# SensorNodeUsb.net
KiCad netlist of a schematic drawn in EAGLE
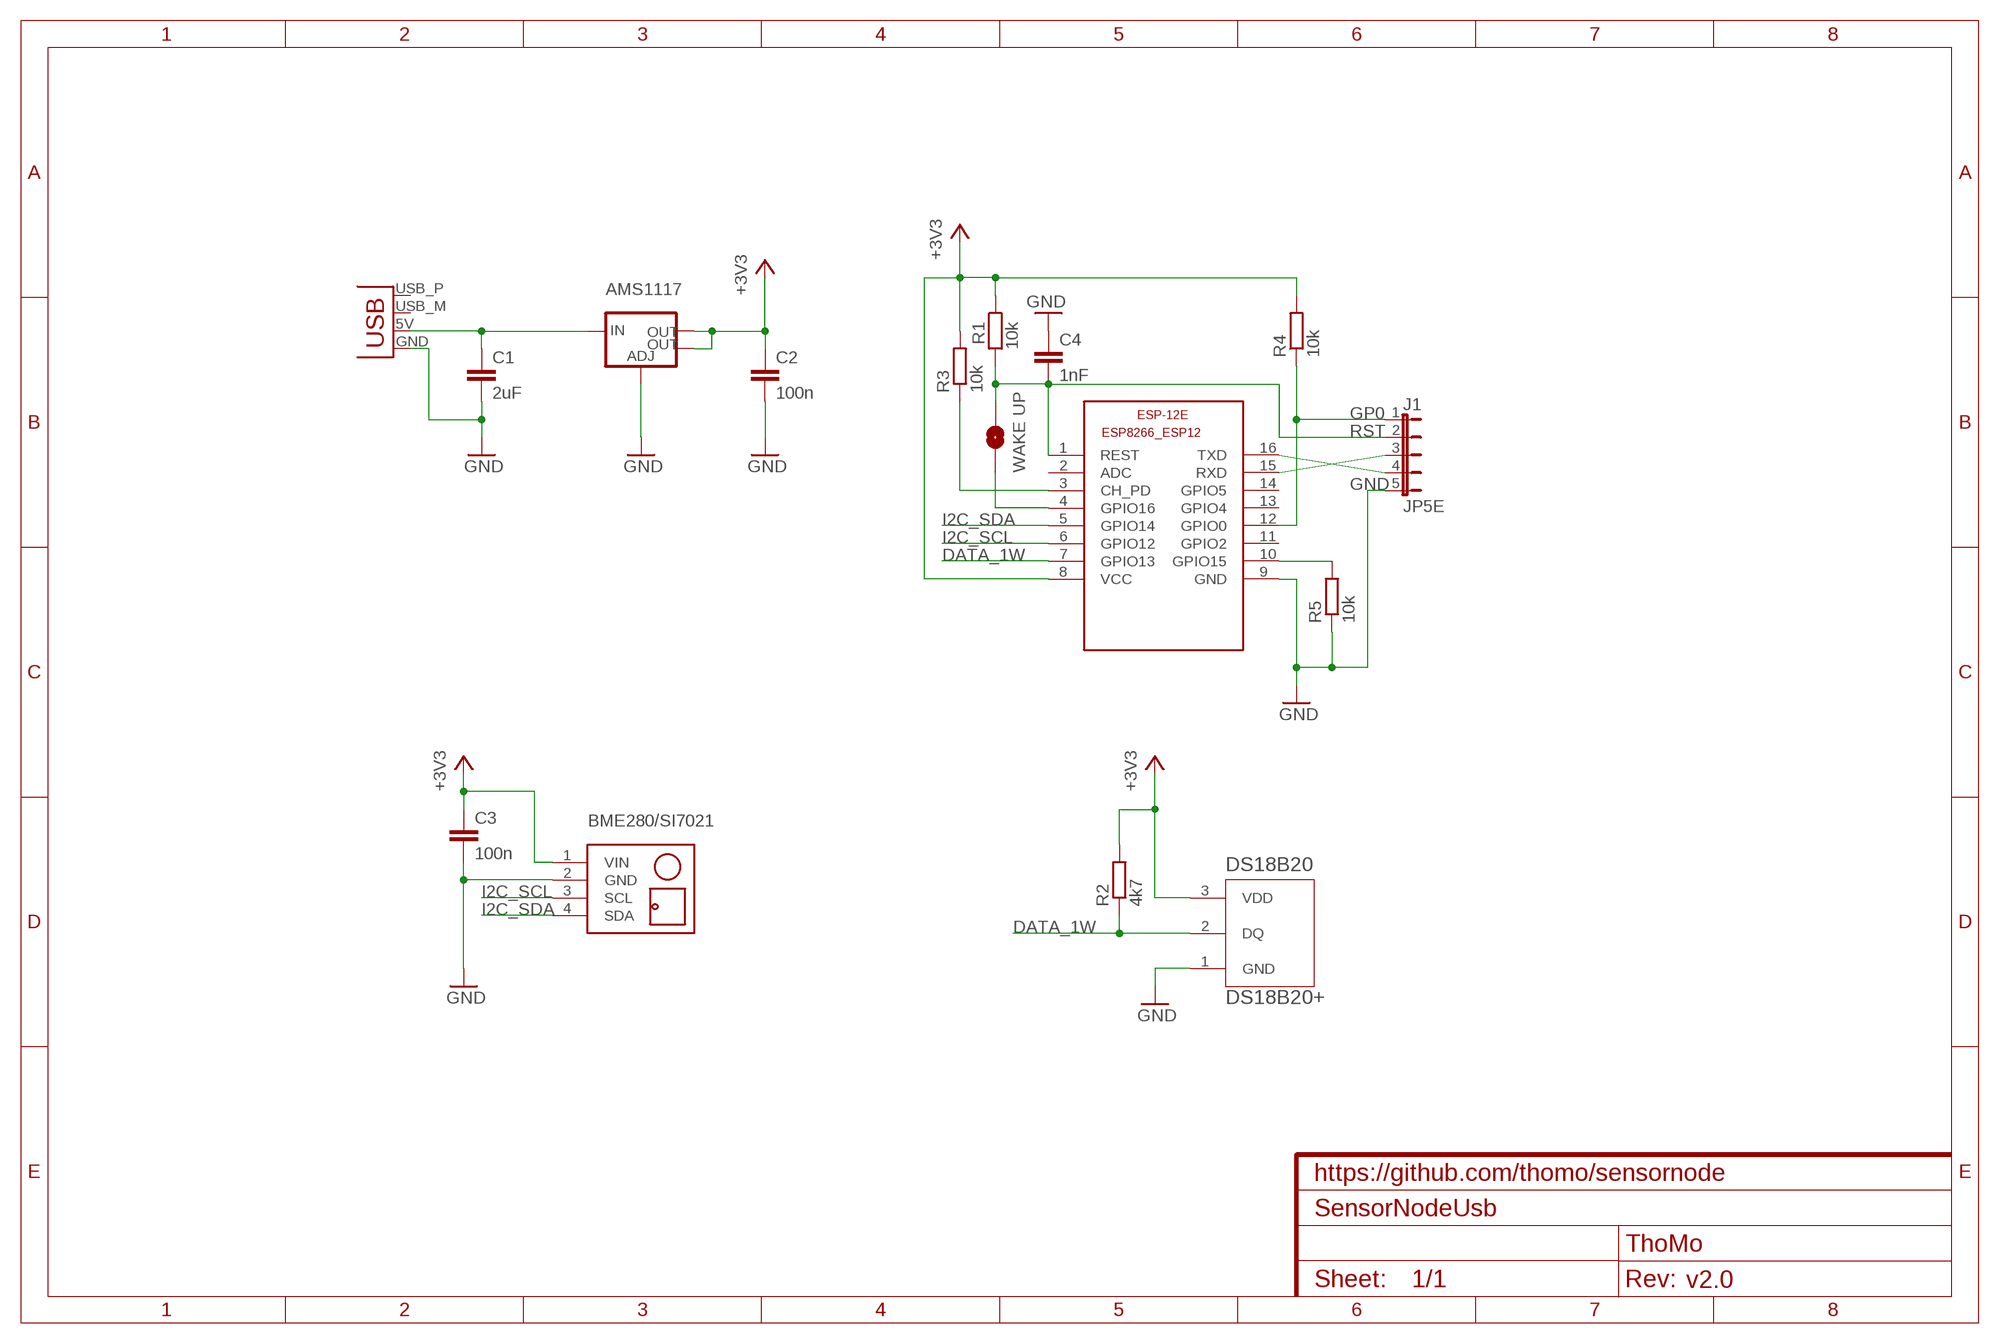
[diagram p0: schematic, sheet 1]

(export (version "E")
  (design (tool "Eeschema 10.0.6"))
  (components
    (comp (ref "AMS1117")
      (value "V_REG_LM1117SOT223")
      (footprint "eagle-import:SOT223")
      (libsource (lib "eagle-import") (part "V_REG_LM1117SOT223"))
    )
    (comp (ref "BME280/SI7021")
      (value "TEMP-HUM-PRES-BME280")
      (footprint "eagle-import:TEMP-HUM-PRES-BME280")
      (libsource (lib "eagle-import") (part "TEMP-HUM-PRES-BME280"))
    )
    (comp (ref "C1")
      (value "2uF")
      (footprint "eagle-import:C1206")
      (libsource (lib "eagle-import") (part "C-EUC1206"))
    )
    (comp (ref "C2")
      (value "100n")
      (footprint "eagle-import:C1206")
      (libsource (lib "eagle-import") (part "C-EUC1206"))
    )
    (comp (ref "C3")
      (value "100n")
      (footprint "eagle-import:C1206K")
      (libsource (lib "eagle-import") (part "C-EUC1206K"))
    )
    (comp (ref "C4")
      (value "1nF")
      (footprint "eagle-import:C1206")
      (libsource (lib "eagle-import") (part "C-EUC1206"))
    )
    (comp (ref "DS18B20")
      (value "DS18B20+")
      (footprint "eagle-import:TO-92")
      (libsource (lib "eagle-import") (part "DS18B20+"))
    )
    (comp (ref "ESP-12E")
      (value "ESP8266-12")
      (footprint "eagle-import:ESP8266-ESP12")
      (libsource (lib "eagle-import") (part "ESP8266-12"))
    )
    (comp (ref "J1")
      (value "JP5E")
      (footprint "eagle-import:JP5")
      (libsource (lib "eagle-import") (part "JP5E"))
    )
    (comp (ref "R1")
      (value "10k")
      (footprint "eagle-import:M1206")
      (libsource (lib "eagle-import") (part "R-EU_M1206"))
    )
    (comp (ref "R2")
      (value "4k7")
      (footprint "eagle-import:M1206")
      (libsource (lib "eagle-import") (part "R-EU_M1206"))
    )
    (comp (ref "R3")
      (value "10k")
      (footprint "eagle-import:M1206")
      (libsource (lib "eagle-import") (part "R-EU_M1206"))
    )
    (comp (ref "R4")
      (value "10k")
      (footprint "eagle-import:M1206")
      (libsource (lib "eagle-import") (part "R-EU_M1206"))
    )
    (comp (ref "R5")
      (value "10k")
      (footprint "eagle-import:M1206")
      (libsource (lib "eagle-import") (part "R-EU_M1206"))
    )
    (comp (ref "WAKEUP")
      (value "WAKE UP")
      (footprint "eagle-import:SMT-JUMPER_2_NO_SILK")
      (libsource (lib "eagle-import") (part "JUMPER-SMT_2_NO_SILK"))
    )
    (comp (ref "X2")
      (value "USBPCB")
      (footprint "eagle-import:USB-A-PCB")
      (libsource (lib "eagle-import") (part "USBPCB"))
    )
  )
  (nets
    (net (code "1") (name "+3V3") (class "Default")
      (node (ref "AMS1117") (pin "2") (pinfunction "OUT_2") (pintype "output"))
      (node (ref "AMS1117") (pin "4") (pinfunction "OUT_4") (pintype "output"))
      (node (ref "BME280/SI7021") (pin "1") (pinfunction "VIN_1") (pintype "power_in"))
      (node (ref "C2") (pin "1") (pinfunction "1_1") (pintype "passive"))
      (node (ref "C3") (pin "1") (pinfunction "1_1") (pintype "passive"))
      (node (ref "DS18B20") (pin "3") (pinfunction "VDD_3") (pintype "power_in"))
      (node (ref "ESP-12E") (pin "8") (pinfunction "VCC_8") (pintype "bidirectional"))
      (node (ref "R1") (pin "1") (pinfunction "1_1") (pintype "passive"))
      (node (ref "R2") (pin "2") (pinfunction "2_2") (pintype "passive"))
      (node (ref "R3") (pin "2") (pinfunction "2_2") (pintype "passive"))
      (node (ref "R4") (pin "2") (pinfunction "2_2") (pintype "passive"))
    )
    (net (code "2") (name "/DATA_1W") (class "Default")
      (node (ref "DS18B20") (pin "2") (pinfunction "DQ_2") (pintype "bidirectional"))
      (node (ref "ESP-12E") (pin "7") (pinfunction "GPIO13_7") (pintype "bidirectional"))
      (node (ref "R2") (pin "1") (pinfunction "1_1") (pintype "passive"))
    )
    (net (code "3") (name "/GP0") (class "Default")
      (node (ref "ESP-12E") (pin "12") (pinfunction "GPIO0_12") (pintype "bidirectional"))
      (node (ref "J1") (pin "1") (pinfunction "1_1") (pintype "passive"))
      (node (ref "R4") (pin "1") (pinfunction "1_1") (pintype "passive"))
    )
    (net (code "4") (name "/I2C_SCL") (class "Default")
      (node (ref "BME280/SI7021") (pin "3") (pinfunction "SCL_3") (pintype "bidirectional"))
      (node (ref "ESP-12E") (pin "6") (pinfunction "GPIO12_6") (pintype "bidirectional"))
    )
    (net (code "5") (name "/I2C_SDA") (class "Default")
      (node (ref "BME280/SI7021") (pin "4") (pinfunction "SDA_4") (pintype "bidirectional"))
      (node (ref "ESP-12E") (pin "5") (pinfunction "GPIO14_5") (pintype "bidirectional"))
    )
    (net (code "6") (name "/RST") (class "Default")
      (node (ref "C4") (pin "2") (pinfunction "2_2") (pintype "passive"))
      (node (ref "ESP-12E") (pin "1") (pinfunction "REST_1") (pintype "bidirectional"))
      (node (ref "J1") (pin "2") (pinfunction "2_2") (pintype "passive"))
      (node (ref "R1") (pin "2") (pinfunction "2_2") (pintype "passive"))
      (node (ref "WAKEUP") (pin "2") (pinfunction "2_2") (pintype "passive"))
    )
    (net (code "7") (name "GND") (class "Default")
      (node (ref "AMS1117") (pin "1") (pinfunction "ADJ_1") (pintype "input"))
      (node (ref "BME280/SI7021") (pin "2") (pinfunction "GND_2") (pintype "power_in"))
      (node (ref "C1") (pin "2") (pinfunction "2_2") (pintype "passive"))
      (node (ref "C2") (pin "2") (pinfunction "2_2") (pintype "passive"))
      (node (ref "C3") (pin "2") (pinfunction "2_2") (pintype "passive"))
      (node (ref "C4") (pin "1") (pinfunction "1_1") (pintype "passive"))
      (node (ref "DS18B20") (pin "1") (pinfunction "GND_1") (pintype "power_in"))
      (node (ref "ESP-12E") (pin "9") (pinfunction "GND_9") (pintype "bidirectional"))
      (node (ref "J1") (pin "5") (pinfunction "5_5") (pintype "passive"))
      (node (ref "R5") (pin "1") (pinfunction "1_1") (pintype "passive"))
      (node (ref "X2") (pin "GND") (pinfunction "GND_GND") (pintype "bidirectional"))
    )
    (net (code "8") (name "Net-(AMS1117-IN)") (class "Default")
      (node (ref "AMS1117") (pin "3") (pinfunction "IN_3") (pintype "input"))
      (node (ref "C1") (pin "1") (pinfunction "1_1") (pintype "passive"))
      (node (ref "X2") (pin "5V") (pinfunction "VBUS_5V") (pintype "bidirectional"))
    )
    (net (code "9") (name "Net-(ESP-12E-CH_PD)") (class "Default")
      (node (ref "ESP-12E") (pin "3") (pinfunction "CH_PD_3") (pintype "bidirectional"))
      (node (ref "R3") (pin "1") (pinfunction "1_1") (pintype "passive"))
    )
    (net (code "10") (name "Net-(ESP-12E-GPIO15)") (class "Default")
      (node (ref "ESP-12E") (pin "10") (pinfunction "GPIO15_10") (pintype "bidirectional"))
      (node (ref "R5") (pin "2") (pinfunction "2_2") (pintype "passive"))
    )
    (net (code "11") (name "Net-(ESP-12E-GPIO16)") (class "Default")
      (node (ref "ESP-12E") (pin "4") (pinfunction "GPIO16_4") (pintype "bidirectional"))
      (node (ref "WAKEUP") (pin "1") (pinfunction "1_1") (pintype "passive"))
    )
    (net (code "12") (name "Net-(ESP-12E-RXD)") (class "Default")
      (node (ref "ESP-12E") (pin "15") (pinfunction "RXD_15") (pintype "bidirectional"))
      (node (ref "J1") (pin "3") (pinfunction "3_3") (pintype "passive"))
    )
    (net (code "13") (name "Net-(ESP-12E-TXD)") (class "Default")
      (node (ref "ESP-12E") (pin "16") (pinfunction "TXD_16") (pintype "bidirectional"))
      (node (ref "J1") (pin "4") (pinfunction "4_4") (pintype "passive"))
    )
    (net (code "14") (name "unconnected-(ESP-12E-ADC-Pad2)") (class "Default")
      (node (ref "ESP-12E") (pin "2") (pinfunction "ADC_2") (pintype "bidirectional"))
    )
    (net (code "15") (name "unconnected-(ESP-12E-GPIO2-Pad11)") (class "Default")
      (node (ref "ESP-12E") (pin "11") (pinfunction "GPIO2_11") (pintype "bidirectional"))
    )
    (net (code "16") (name "unconnected-(ESP-12E-GPIO4-Pad13)") (class "Default")
      (node (ref "ESP-12E") (pin "13") (pinfunction "GPIO4_13") (pintype "bidirectional"))
    )
    (net (code "17") (name "unconnected-(ESP-12E-GPIO5-Pad14)") (class "Default")
      (node (ref "ESP-12E") (pin "14") (pinfunction "GPIO5_14") (pintype "bidirectional"))
    )
    (net (code "18") (name "unconnected-(X2-D+-PadUSB_P)") (class "Default")
      (node (ref "X2") (pin "USB_P") (pinfunction "D+_USB_P") (pintype "bidirectional"))
    )
    (net (code "19") (name "unconnected-(X2-D--PadUSB_M)") (class "Default")
      (node (ref "X2") (pin "USB_M") (pinfunction "D-_USB_M") (pintype "bidirectional"))
    )
  )
)
